# cc2652r_rev_e_ipx.net
KiCad netlist of a schematic drawn in EAGLE
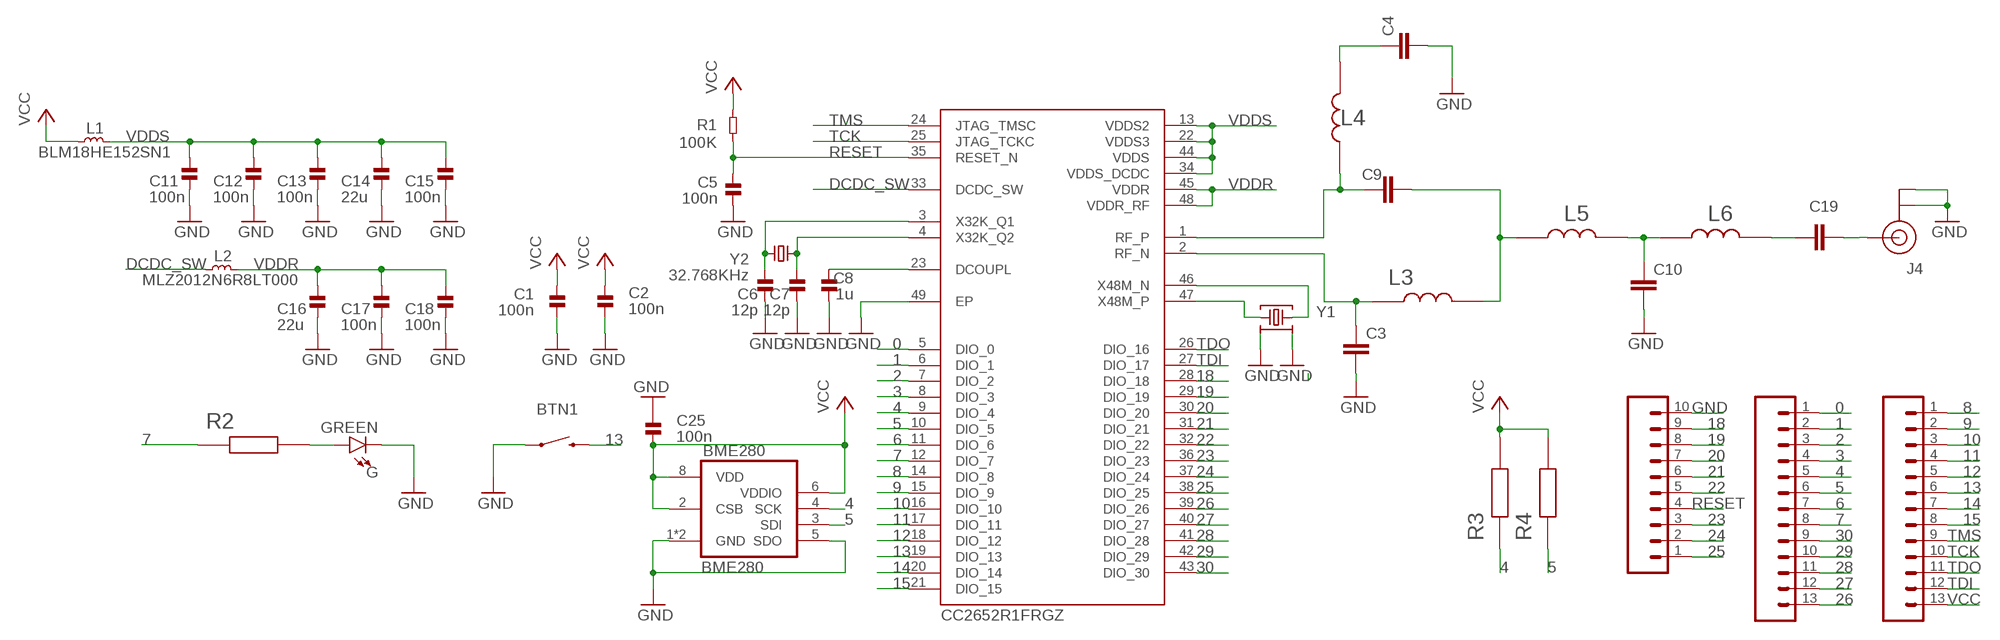
[diagram p0: schematic, sheet 1]

(export (version "E")
  (design (tool "Eeschema 10.0.6"))
  (components
    (comp (ref "BME280")
      (value "BME280")
      (footprint "eagle-import:BME280")
      (libsource (lib "eagle-import") (part "BME280"))
    )
    (comp (ref "BTN1")
      (value "MOMENTARY-SWITCH-SPST-SMD-4.6X2.8MM")
      (footprint "eagle-import:TACTILE_SWITCH_SMD_4.6X2.8MM")
      (libsource (lib "eagle-import") (part "MOMENTARY-SWITCH-SPST-SMD-4.6X2.8MM"))
    )
    (comp (ref "C1")
      (value "100n")
      (footprint "eagle-import:_PKG_C_0402")
      (libsource (lib "eagle-import") (part "CAP-0402"))
    )
    (comp (ref "C2")
      (value "100n")
      (footprint "eagle-import:_PKG_C_0402")
      (libsource (lib "eagle-import") (part "CAP-0402"))
    )
    (comp (ref "C3")
      (value "1pF")
      (footprint "eagle-import:CAPC1005X40N")
      (fields (field (name "MF") "Yageo") (field (name "MP") "RC0402FR-073M6L"))
      (libsource (lib "eagle-import") (part "CAP0402"))
    )
    (comp (ref "C4")
      (value "12pF")
      (footprint "eagle-import:CAPC1005X40N")
      (fields (field (name "MF") "Yageo") (field (name "MP") "RC0402FR-073M6L"))
      (libsource (lib "eagle-import") (part "CAP0402"))
    )
    (comp (ref "C5")
      (value "100n")
      (footprint "eagle-import:_PKG_C_0402")
      (libsource (lib "eagle-import") (part "CAP-0402"))
    )
    (comp (ref "C6")
      (value "12p")
      (footprint "eagle-import:_PKG_C_0402")
      (libsource (lib "eagle-import") (part "CAP-0402"))
    )
    (comp (ref "C7")
      (value "12p")
      (footprint "eagle-import:_PKG_C_0402")
      (libsource (lib "eagle-import") (part "CAP-0402"))
    )
    (comp (ref "C8")
      (value "1u")
      (footprint "eagle-import:_PKG_C_0402")
      (libsource (lib "eagle-import") (part "CAP-0402"))
    )
    (comp (ref "C9")
      (value "1pF")
      (footprint "eagle-import:CAPC1005X40N")
      (fields (field (name "MF") "Yageo") (field (name "MP") "RC0402FR-073M6L"))
      (libsource (lib "eagle-import") (part "CAP0402"))
    )
    (comp (ref "C10")
      (value "1pF")
      (footprint "eagle-import:CAPC1005X40N")
      (fields (field (name "MF") "Yageo") (field (name "MP") "RC0402FR-073M6L"))
      (libsource (lib "eagle-import") (part "CAP0402"))
    )
    (comp (ref "C11")
      (value "100n")
      (footprint "eagle-import:_PKG_C_0402")
      (libsource (lib "eagle-import") (part "CAP-0402"))
    )
    (comp (ref "C12")
      (value "100n")
      (footprint "eagle-import:_PKG_C_0402")
      (libsource (lib "eagle-import") (part "CAP-0402"))
    )
    (comp (ref "C13")
      (value "100n")
      (footprint "eagle-import:_PKG_C_0402")
      (libsource (lib "eagle-import") (part "CAP-0402"))
    )
    (comp (ref "C14")
      (value "22u")
      (footprint "eagle-import:_PKG_C_0805")
      (libsource (lib "eagle-import") (part "CAP-0805"))
    )
    (comp (ref "C15")
      (value "100n")
      (footprint "eagle-import:_PKG_C_0402")
      (libsource (lib "eagle-import") (part "CAP-0402"))
    )
    (comp (ref "C16")
      (value "22u")
      (footprint "eagle-import:_PKG_C_0805")
      (libsource (lib "eagle-import") (part "CAP-0805"))
    )
    (comp (ref "C17")
      (value "100n")
      (footprint "eagle-import:_PKG_C_0402")
      (libsource (lib "eagle-import") (part "CAP-0402"))
    )
    (comp (ref "C18")
      (value "100n")
      (footprint "eagle-import:_PKG_C_0402")
      (libsource (lib "eagle-import") (part "CAP-0402"))
    )
    (comp (ref "C19")
      (value "12pF")
      (footprint "eagle-import:CAPC1005X40N")
      (fields (field (name "MF") "Yageo") (field (name "MP") "RC0402FR-073M6L"))
      (libsource (lib "eagle-import") (part "CAP0402"))
    )
    (comp (ref "C25")
      (value "100n")
      (footprint "eagle-import:_PKG_C_0402")
      (libsource (lib "eagle-import") (part "CAP-0402"))
    )
    (comp (ref "G")
      (value "GREEN")
      (footprint "eagle-import:LED-0603")
      (libsource (lib "eagle-import") (part "LED-GREEN0603"))
    )
    (comp (ref "IC3")
      (value "CC2652R1FRGZ")
      (footprint "eagle-import:QFN50P700X700X100-49N")
      (fields
        (field (name "MANUFACTURER_PART_NUMBER") "CC2652R1FRGZT")
        (field (name "MOUSER_PART_NUMBER") "595-CC2652R1FRGZT")
      )
      (libsource (lib "eagle-import") (part "WMCU-CC2652R1FRGZ"))
    )
    (comp (ref "J1")
      (value "CONN_051.27MM")
      (footprint "eagle-import:1X05_1.27MM")
      (libsource (lib "eagle-import") (part "CONN_051.27MM"))
    )
    (comp (ref "J2")
      (value "CONN_051.27MM")
      (footprint "eagle-import:1X05_1.27MM")
      (libsource (lib "eagle-import") (part "CONN_051.27MM"))
    )
    (comp (ref "J3")
      (value "CONN_061.27MM")
      (footprint "eagle-import:1X06_1.27MM")
      (libsource (lib "eagle-import") (part "CONN_061.27MM"))
    )
    (comp (ref "J4")
      (value "U.FL")
      (footprint "eagle-import:U.FL")
      (libsource (lib "eagle-import") (part "U.FL"))
    )
    (comp (ref "L1")
      (value "BLM18HE152SN1")
      (footprint "eagle-import:_PKG_L_0603")
      (libsource (lib "eagle-import") (part "INDUCTOR-0603"))
    )
    (comp (ref "L2")
      (value "MLZ2012N6R8LT000")
      (footprint "eagle-import:_PKG_C_0805")
      (libsource (lib "eagle-import") (part "INDUCTOR-0805"))
    )
    (comp (ref "L3")
      (value "2.4nH")
      (footprint "eagle-import:INDC1005X40N")
      (fields (field (name "MF") "Yageo") (field (name "MP") "RC0402FR-073M6L"))
      (libsource (lib "eagle-import") (part "IND0402IND0402"))
    )
    (comp (ref "L4")
      (value "2.4nH")
      (footprint "eagle-import:INDC1005X40N")
      (fields (field (name "MF") "Yageo") (field (name "MP") "RC0402FR-073M6L"))
      (libsource (lib "eagle-import") (part "IND0402IND0402"))
    )
    (comp (ref "L5")
      (value "2nH")
      (footprint "eagle-import:INDC1005X40N")
      (fields (field (name "MF") "Yageo") (field (name "MP") "RC0402FR-073M6L"))
      (libsource (lib "eagle-import") (part "IND0402IND0402"))
    )
    (comp (ref "L6")
      (value "2nH")
      (footprint "eagle-import:INDC1005X40N")
      (fields (field (name "MF") "Yageo") (field (name "MP") "RC0402FR-073M6L"))
      (libsource (lib "eagle-import") (part "IND0402IND0402"))
    )
    (comp (ref "R1")
      (value "100K")
      (footprint "eagle-import:_PKG_C_0402")
      (libsource (lib "eagle-import") (part "RES-0402"))
    )
    (comp (ref "R2")
      (value "2.2k")
      (footprint "eagle-import:RESC1005X40N")
      (fields (field (name "MF") "Yageo") (field (name "MP") "RC0402FR-073M6L"))
      (libsource (lib "eagle-import") (part "RES0402"))
    )
    (comp (ref "R3")
      (value "4.7k")
      (footprint "eagle-import:RESC1005X40N")
      (fields (field (name "MF") "Yageo") (field (name "MP") "RC0402FR-073M6L"))
      (libsource (lib "eagle-import") (part "RES0402"))
    )
    (comp (ref "R4")
      (value "4.7k")
      (footprint "eagle-import:RESC1005X40N")
      (fields (field (name "MF") "Yageo") (field (name "MP") "RC0402FR-073M6L"))
      (libsource (lib "eagle-import") (part "RES0402"))
    )
    (comp (ref "Y1")
      (value "Q22FA12800150")
      (footprint "eagle-import:XTAL-4P-2016")
      (fields (field (name "DIGIKEY_PART") "1253-2042-1-ND") (field (name "MFG_PART") "CX2016DB48000C0FPLC1"))
      (libsource (lib "eagle-import") (part "48.000MHZ_CX2016DB48000C0FPLC1"))
    )
    (comp (ref "Y2")
      (value "32.768KHz")
      (footprint "eagle-import:XTAL-2P-3215")
      (fields (field (name "LCSC_PART") "C32346") (field (name "MFG_PART") "Q13FC1350000400"))
      (libsource (lib "eagle-import") (part "32.768KHZ_Q13FC1350000400"))
    )
  )
  (nets
    (net (code "1") (name "/0") (class "Default")
      (node (ref "IC3") (pin "5") (pinfunction "DIO_0_5") (pintype "bidirectional"))
      (node (ref "J1") (pin "1") (pinfunction "1_1") (pintype "passive"))
    )
    (net (code "2") (name "/1") (class "Default")
      (node (ref "IC3") (pin "6") (pinfunction "DIO_1_6") (pintype "bidirectional"))
      (node (ref "J1") (pin "2") (pinfunction "2_2") (pintype "passive"))
    )
    (net (code "3") (name "/2") (class "Default")
      (node (ref "IC3") (pin "7") (pinfunction "DIO_2_7") (pintype "bidirectional"))
      (node (ref "J1") (pin "3") (pinfunction "3_3") (pintype "passive"))
    )
    (net (code "4") (name "/3") (class "Default")
      (node (ref "IC3") (pin "8") (pinfunction "DIO_3_8") (pintype "bidirectional"))
      (node (ref "J1") (pin "4") (pinfunction "4_4") (pintype "passive"))
    )
    (net (code "5") (name "/4") (class "Default")
      (node (ref "BME280") (pin "4") (pinfunction "SCK_4") (pintype "bidirectional"))
      (node (ref "IC3") (pin "9") (pinfunction "DIO_4_9") (pintype "bidirectional"))
      (node (ref "J1") (pin "5") (pinfunction "5_5") (pintype "passive"))
      (node (ref "R3") (pin "1") (pinfunction "1_1") (pintype "passive"))
    )
    (net (code "6") (name "/5") (class "Default")
      (node (ref "BME280") (pin "3") (pinfunction "SDI_3") (pintype "bidirectional"))
      (node (ref "IC3") (pin "10") (pinfunction "DIO_5_10") (pintype "bidirectional"))
      (node (ref "J1") (pin "6") (pinfunction "6_6") (pintype "passive"))
      (node (ref "R4") (pin "1") (pinfunction "1_1") (pintype "passive"))
    )
    (net (code "7") (name "/6") (class "Default")
      (node (ref "IC3") (pin "11") (pinfunction "DIO_6_11") (pintype "bidirectional"))
      (node (ref "J1") (pin "7") (pinfunction "7_7") (pintype "passive"))
    )
    (net (code "8") (name "/7") (class "Default")
      (node (ref "IC3") (pin "12") (pinfunction "DIO_7_12") (pintype "bidirectional"))
      (node (ref "J1") (pin "8") (pinfunction "8_8") (pintype "passive"))
      (node (ref "R2") (pin "1") (pinfunction "1_1") (pintype "passive"))
    )
    (net (code "9") (name "/8") (class "Default")
      (node (ref "IC3") (pin "14") (pinfunction "DIO_8_14") (pintype "bidirectional"))
      (node (ref "J2") (pin "1") (pinfunction "1_1") (pintype "passive"))
    )
    (net (code "10") (name "/9") (class "Default")
      (node (ref "IC3") (pin "15") (pinfunction "DIO_9_15") (pintype "bidirectional"))
      (node (ref "J2") (pin "2") (pinfunction "2_2") (pintype "passive"))
    )
    (net (code "11") (name "/10") (class "Default")
      (node (ref "IC3") (pin "16") (pinfunction "DIO_10_16") (pintype "bidirectional"))
      (node (ref "J2") (pin "3") (pinfunction "3_3") (pintype "passive"))
    )
    (net (code "12") (name "/11") (class "Default")
      (node (ref "IC3") (pin "17") (pinfunction "DIO_11_17") (pintype "bidirectional"))
      (node (ref "J2") (pin "4") (pinfunction "4_4") (pintype "passive"))
    )
    (net (code "13") (name "/12") (class "Default")
      (node (ref "IC3") (pin "18") (pinfunction "DIO_12_18") (pintype "bidirectional"))
      (node (ref "J2") (pin "5") (pinfunction "5_5") (pintype "passive"))
    )
    (net (code "14") (name "/13") (class "Default")
      (node (ref "BTN1") (pin "3") (pinfunction "2_3") (pintype "passive"))
      (node (ref "BTN1") (pin "4") (pinfunction "2_4") (pintype "passive"))
      (node (ref "IC3") (pin "19") (pinfunction "DIO_13_19") (pintype "bidirectional"))
      (node (ref "J2") (pin "6") (pinfunction "6_6") (pintype "passive"))
    )
    (net (code "15") (name "/14") (class "Default")
      (node (ref "IC3") (pin "20") (pinfunction "DIO_14_20") (pintype "bidirectional"))
      (node (ref "J2") (pin "7") (pinfunction "7_7") (pintype "passive"))
    )
    (net (code "16") (name "/15") (class "Default")
      (node (ref "IC3") (pin "21") (pinfunction "DIO_15_21") (pintype "bidirectional"))
      (node (ref "J2") (pin "8") (pinfunction "8_8") (pintype "passive"))
    )
    (net (code "17") (name "/18") (class "Default")
      (node (ref "IC3") (pin "28") (pinfunction "DIO_18_28") (pintype "bidirectional"))
      (node (ref "J3") (pin "9") (pinfunction "9_9") (pintype "passive"))
    )
    (net (code "18") (name "/19") (class "Default")
      (node (ref "IC3") (pin "29") (pinfunction "DIO_19_29") (pintype "bidirectional"))
      (node (ref "J3") (pin "8") (pinfunction "8_8") (pintype "passive"))
    )
    (net (code "19") (name "/20") (class "Default")
      (node (ref "IC3") (pin "30") (pinfunction "DIO_20_30") (pintype "bidirectional"))
      (node (ref "J3") (pin "7") (pinfunction "7_7") (pintype "passive"))
    )
    (net (code "20") (name "/21") (class "Default")
      (node (ref "IC3") (pin "31") (pinfunction "DIO_21_31") (pintype "bidirectional"))
      (node (ref "J3") (pin "6") (pinfunction "6_6") (pintype "passive"))
    )
    (net (code "21") (name "/22") (class "Default")
      (node (ref "IC3") (pin "32") (pinfunction "DIO_22_32") (pintype "bidirectional"))
      (node (ref "J3") (pin "5") (pinfunction "5_5") (pintype "passive"))
    )
    (net (code "22") (name "/23") (class "Default")
      (node (ref "IC3") (pin "36") (pinfunction "DIO_23_36") (pintype "bidirectional"))
      (node (ref "J3") (pin "3") (pinfunction "3_3") (pintype "passive"))
    )
    (net (code "23") (name "/24") (class "Default")
      (node (ref "IC3") (pin "37") (pinfunction "DIO_24_37") (pintype "bidirectional"))
      (node (ref "J3") (pin "2") (pinfunction "2_2") (pintype "passive"))
    )
    (net (code "24") (name "/25") (class "Default")
      (node (ref "IC3") (pin "38") (pinfunction "DIO_25_38") (pintype "bidirectional"))
      (node (ref "J3") (pin "1") (pinfunction "1_1") (pintype "passive"))
    )
    (net (code "25") (name "/26") (class "Default")
      (node (ref "IC3") (pin "39") (pinfunction "DIO_26_39") (pintype "bidirectional"))
      (node (ref "J1") (pin "13") (pinfunction "13_13") (pintype "passive"))
    )
    (net (code "26") (name "/27") (class "Default")
      (node (ref "IC3") (pin "40") (pinfunction "DIO_27_40") (pintype "bidirectional"))
      (node (ref "J1") (pin "12") (pinfunction "12_12") (pintype "passive"))
    )
    (net (code "27") (name "/28") (class "Default")
      (node (ref "IC3") (pin "41") (pinfunction "DIO_28_41") (pintype "bidirectional"))
      (node (ref "J1") (pin "11") (pinfunction "11_11") (pintype "passive"))
    )
    (net (code "28") (name "/29") (class "Default")
      (node (ref "IC3") (pin "42") (pinfunction "DIO_29_42") (pintype "bidirectional"))
      (node (ref "J1") (pin "10") (pinfunction "10_10") (pintype "passive"))
    )
    (net (code "29") (name "/30") (class "Default")
      (node (ref "IC3") (pin "43") (pinfunction "DIO_30_43") (pintype "bidirectional"))
      (node (ref "J1") (pin "9") (pinfunction "9_9") (pintype "passive"))
    )
    (net (code "30") (name "/DCDC_SW") (class "Default")
      (node (ref "IC3") (pin "33") (pinfunction "DCDC_SW_33") (pintype "bidirectional"))
      (node (ref "L2") (pin "1") (pinfunction "1_1") (pintype "passive"))
    )
    (net (code "31") (name "/RESET") (class "Default")
      (node (ref "C5") (pin "2") (pinfunction "2_2") (pintype "passive"))
      (node (ref "IC3") (pin "35") (pinfunction "RESET_N_35") (pintype "bidirectional"))
      (node (ref "J3") (pin "4") (pinfunction "4_4") (pintype "passive"))
      (node (ref "R1") (pin "1") (pinfunction "1_1") (pintype "passive"))
    )
    (net (code "32") (name "/TCK") (class "Default")
      (node (ref "IC3") (pin "25") (pinfunction "JTAG_TCKC_25") (pintype "bidirectional"))
      (node (ref "J2") (pin "10") (pinfunction "10_10") (pintype "passive"))
    )
    (net (code "33") (name "/TDI") (class "Default")
      (node (ref "IC3") (pin "27") (pinfunction "DIO_17_27") (pintype "bidirectional"))
      (node (ref "J2") (pin "12") (pinfunction "12_12") (pintype "passive"))
    )
    (net (code "34") (name "/TDO") (class "Default")
      (node (ref "IC3") (pin "26") (pinfunction "DIO_16_26") (pintype "bidirectional"))
      (node (ref "J2") (pin "11") (pinfunction "11_11") (pintype "passive"))
    )
    (net (code "35") (name "/TMS") (class "Default")
      (node (ref "IC3") (pin "24") (pinfunction "JTAG_TMSC_24") (pintype "bidirectional"))
      (node (ref "J2") (pin "9") (pinfunction "9_9") (pintype "passive"))
    )
    (net (code "36") (name "/VDDR") (class "Default")
      (node (ref "C16") (pin "1") (pinfunction "1_1") (pintype "passive"))
      (node (ref "C17") (pin "1") (pinfunction "1_1") (pintype "passive"))
      (node (ref "C18") (pin "1") (pinfunction "1_1") (pintype "passive"))
      (node (ref "IC3") (pin "45") (pinfunction "VDDR_45") (pintype "bidirectional"))
      (node (ref "IC3") (pin "48") (pinfunction "VDDR_RF_48") (pintype "bidirectional"))
      (node (ref "L2") (pin "2") (pinfunction "2_2") (pintype "passive"))
    )
    (net (code "37") (name "/VDDS") (class "Default")
      (node (ref "C11") (pin "1") (pinfunction "1_1") (pintype "passive"))
      (node (ref "C12") (pin "1") (pinfunction "1_1") (pintype "passive"))
      (node (ref "C13") (pin "1") (pinfunction "1_1") (pintype "passive"))
      (node (ref "C14") (pin "1") (pinfunction "1_1") (pintype "passive"))
      (node (ref "C15") (pin "1") (pinfunction "1_1") (pintype "passive"))
      (node (ref "IC3") (pin "13") (pinfunction "VDDS2_13") (pintype "bidirectional"))
      (node (ref "IC3") (pin "22") (pinfunction "VDDS3_22") (pintype "bidirectional"))
      (node (ref "IC3") (pin "34") (pinfunction "VDDS_DCDC_34") (pintype "bidirectional"))
      (node (ref "IC3") (pin "44") (pinfunction "VDDS_44") (pintype "bidirectional"))
      (node (ref "L1") (pin "2") (pinfunction "2_2") (pintype "passive"))
    )
    (net (code "38") (name "GND") (class "Default")
      (node (ref "BME280") (pin "1") (pinfunction "GND_1") (pintype "power_in"))
      (node (ref "BME280") (pin "5") (pinfunction "SDO_5") (pintype "input"))
      (node (ref "BME280") (pin "7") (pinfunction "GND_7") (pintype "power_in"))
      (node (ref "BTN1") (pin "1") (pinfunction "1_1") (pintype "passive"))
      (node (ref "BTN1") (pin "2") (pinfunction "1_2") (pintype "passive"))
      (node (ref "C1") (pin "1") (pinfunction "1_1") (pintype "passive"))
      (node (ref "C10") (pin "2") (pinfunction "2_2") (pintype "passive"))
      (node (ref "C11") (pin "2") (pinfunction "2_2") (pintype "passive"))
      (node (ref "C12") (pin "2") (pinfunction "2_2") (pintype "passive"))
      (node (ref "C13") (pin "2") (pinfunction "2_2") (pintype "passive"))
      (node (ref "C14") (pin "2") (pinfunction "2_2") (pintype "passive"))
      (node (ref "C15") (pin "2") (pinfunction "2_2") (pintype "passive"))
      (node (ref "C16") (pin "2") (pinfunction "2_2") (pintype "passive"))
      (node (ref "C17") (pin "2") (pinfunction "2_2") (pintype "passive"))
      (node (ref "C18") (pin "2") (pinfunction "2_2") (pintype "passive"))
      (node (ref "C2") (pin "1") (pinfunction "1_1") (pintype "passive"))
      (node (ref "C25") (pin "2") (pinfunction "2_2") (pintype "passive"))
      (node (ref "C3") (pin "2") (pinfunction "2_2") (pintype "passive"))
      (node (ref "C4") (pin "2") (pinfunction "2_2") (pintype "passive"))
      (node (ref "C5") (pin "1") (pinfunction "1_1") (pintype "passive"))
      (node (ref "C6") (pin "1") (pinfunction "1_1") (pintype "passive"))
      (node (ref "C7") (pin "1") (pinfunction "1_1") (pintype "passive"))
      (node (ref "C8") (pin "1") (pinfunction "1_1") (pintype "passive"))
      (node (ref "G") (pin "C") (pinfunction "C_C") (pintype "passive"))
      (node (ref "IC3") (pin "49") (pinfunction "EP_49") (pintype "bidirectional"))
      (node (ref "J3") (pin "10") (pinfunction "10_10") (pintype "passive"))
      (node (ref "J4") (pin "1") (pinfunction "GND_1") (pintype "bidirectional"))
      (node (ref "J4") (pin "2") (pinfunction "GND_2") (pintype "bidirectional"))
      (node (ref "Y1") (pin "2") (pinfunction "2_2") (pintype "bidirectional"))
      (node (ref "Y1") (pin "4") (pinfunction "4_4") (pintype "bidirectional"))
    )
    (net (code "39") (name "Net-(C4-Pad1)") (class "Default")
      (node (ref "C4") (pin "1") (pinfunction "1_1") (pintype "passive"))
      (node (ref "L4") (pin "2") (pinfunction "2_2") (pintype "passive"))
    )
    (net (code "40") (name "Net-(C9-Pad2)") (class "Default")
      (node (ref "C9") (pin "2") (pinfunction "2_2") (pintype "passive"))
      (node (ref "L3") (pin "2") (pinfunction "2_2") (pintype "passive"))
      (node (ref "L5") (pin "1") (pinfunction "1_1") (pintype "passive"))
    )
    (net (code "41") (name "Net-(C10-Pad1)") (class "Default")
      (node (ref "C10") (pin "1") (pinfunction "1_1") (pintype "passive"))
      (node (ref "L5") (pin "2") (pinfunction "2_2") (pintype "passive"))
      (node (ref "L6") (pin "1") (pinfunction "1_1") (pintype "passive"))
    )
    (net (code "42") (name "Net-(C19-Pad1)") (class "Default")
      (node (ref "C19") (pin "1") (pinfunction "1_1") (pintype "passive"))
      (node (ref "L6") (pin "2") (pinfunction "2_2") (pintype "passive"))
    )
    (net (code "43") (name "Net-(G-PadA)") (class "Default")
      (node (ref "G") (pin "A") (pinfunction "A_A") (pintype "passive"))
      (node (ref "R2") (pin "2") (pinfunction "2_2") (pintype "passive"))
    )
    (net (code "44") (name "Net-(IC3-DCOUPL)") (class "Default")
      (node (ref "C8") (pin "2") (pinfunction "2_2") (pintype "passive"))
      (node (ref "IC3") (pin "23") (pinfunction "DCOUPL_23") (pintype "bidirectional"))
    )
    (net (code "45") (name "Net-(IC3-RF_N)") (class "Default")
      (node (ref "C3") (pin "1") (pinfunction "1_1") (pintype "passive"))
      (node (ref "IC3") (pin "2") (pinfunction "RF_N_2") (pintype "bidirectional"))
      (node (ref "L3") (pin "1") (pinfunction "1_1") (pintype "passive"))
    )
    (net (code "46") (name "Net-(IC3-RF_P)") (class "Default")
      (node (ref "C9") (pin "1") (pinfunction "1_1") (pintype "passive"))
      (node (ref "IC3") (pin "1") (pinfunction "RF_P_1") (pintype "bidirectional"))
      (node (ref "L4") (pin "1") (pinfunction "1_1") (pintype "passive"))
    )
    (net (code "47") (name "Net-(IC3-X32K_Q1)") (class "Default")
      (node (ref "C6") (pin "2") (pinfunction "2_2") (pintype "passive"))
      (node (ref "IC3") (pin "3") (pinfunction "X32K_Q1_3") (pintype "bidirectional"))
      (node (ref "Y2") (pin "1") (pinfunction "1_1") (pintype "passive"))
    )
    (net (code "48") (name "Net-(IC3-X32K_Q2)") (class "Default")
      (node (ref "C7") (pin "2") (pinfunction "2_2") (pintype "passive"))
      (node (ref "IC3") (pin "4") (pinfunction "X32K_Q2_4") (pintype "bidirectional"))
      (node (ref "Y2") (pin "2") (pinfunction "2_2") (pintype "passive"))
    )
    (net (code "49") (name "Net-(IC3-X48M_N)") (class "Default")
      (node (ref "IC3") (pin "46") (pinfunction "X48M_N_46") (pintype "bidirectional"))
      (node (ref "Y1") (pin "3") (pinfunction "3_3") (pintype "passive"))
    )
    (net (code "50") (name "Net-(IC3-X48M_P)") (class "Default")
      (node (ref "IC3") (pin "47") (pinfunction "X48M_P_47") (pintype "bidirectional"))
      (node (ref "Y1") (pin "1") (pinfunction "1_1") (pintype "passive"))
    )
    (net (code "51") (name "Net-(J4-SIGNAL)") (class "Default")
      (node (ref "C19") (pin "2") (pinfunction "2_2") (pintype "passive"))
      (node (ref "J4") (pin "FEED") (pinfunction "SIGNAL_FEED") (pintype "bidirectional"))
    )
    (net (code "52") (name "VCC") (class "Default")
      (node (ref "BME280") (pin "2") (pinfunction "CSB_2") (pintype "input"))
      (node (ref "BME280") (pin "6") (pinfunction "VDDIO_6") (pintype "power_in"))
      (node (ref "BME280") (pin "8") (pinfunction "VDD_8") (pintype "power_in"))
      (node (ref "C1") (pin "2") (pinfunction "2_2") (pintype "passive"))
      (node (ref "C2") (pin "2") (pinfunction "2_2") (pintype "passive"))
      (node (ref "C25") (pin "1") (pinfunction "1_1") (pintype "passive"))
      (node (ref "J2") (pin "13") (pinfunction "13_13") (pintype "passive"))
      (node (ref "L1") (pin "1") (pinfunction "1_1") (pintype "passive"))
      (node (ref "R1") (pin "2") (pinfunction "2_2") (pintype "passive"))
      (node (ref "R3") (pin "2") (pinfunction "2_2") (pintype "passive"))
      (node (ref "R4") (pin "2") (pinfunction "2_2") (pintype "passive"))
    )
  )
)
